# ece411-t14-MetroKnome.net
KiCad netlist of a schematic drawn in EAGLE
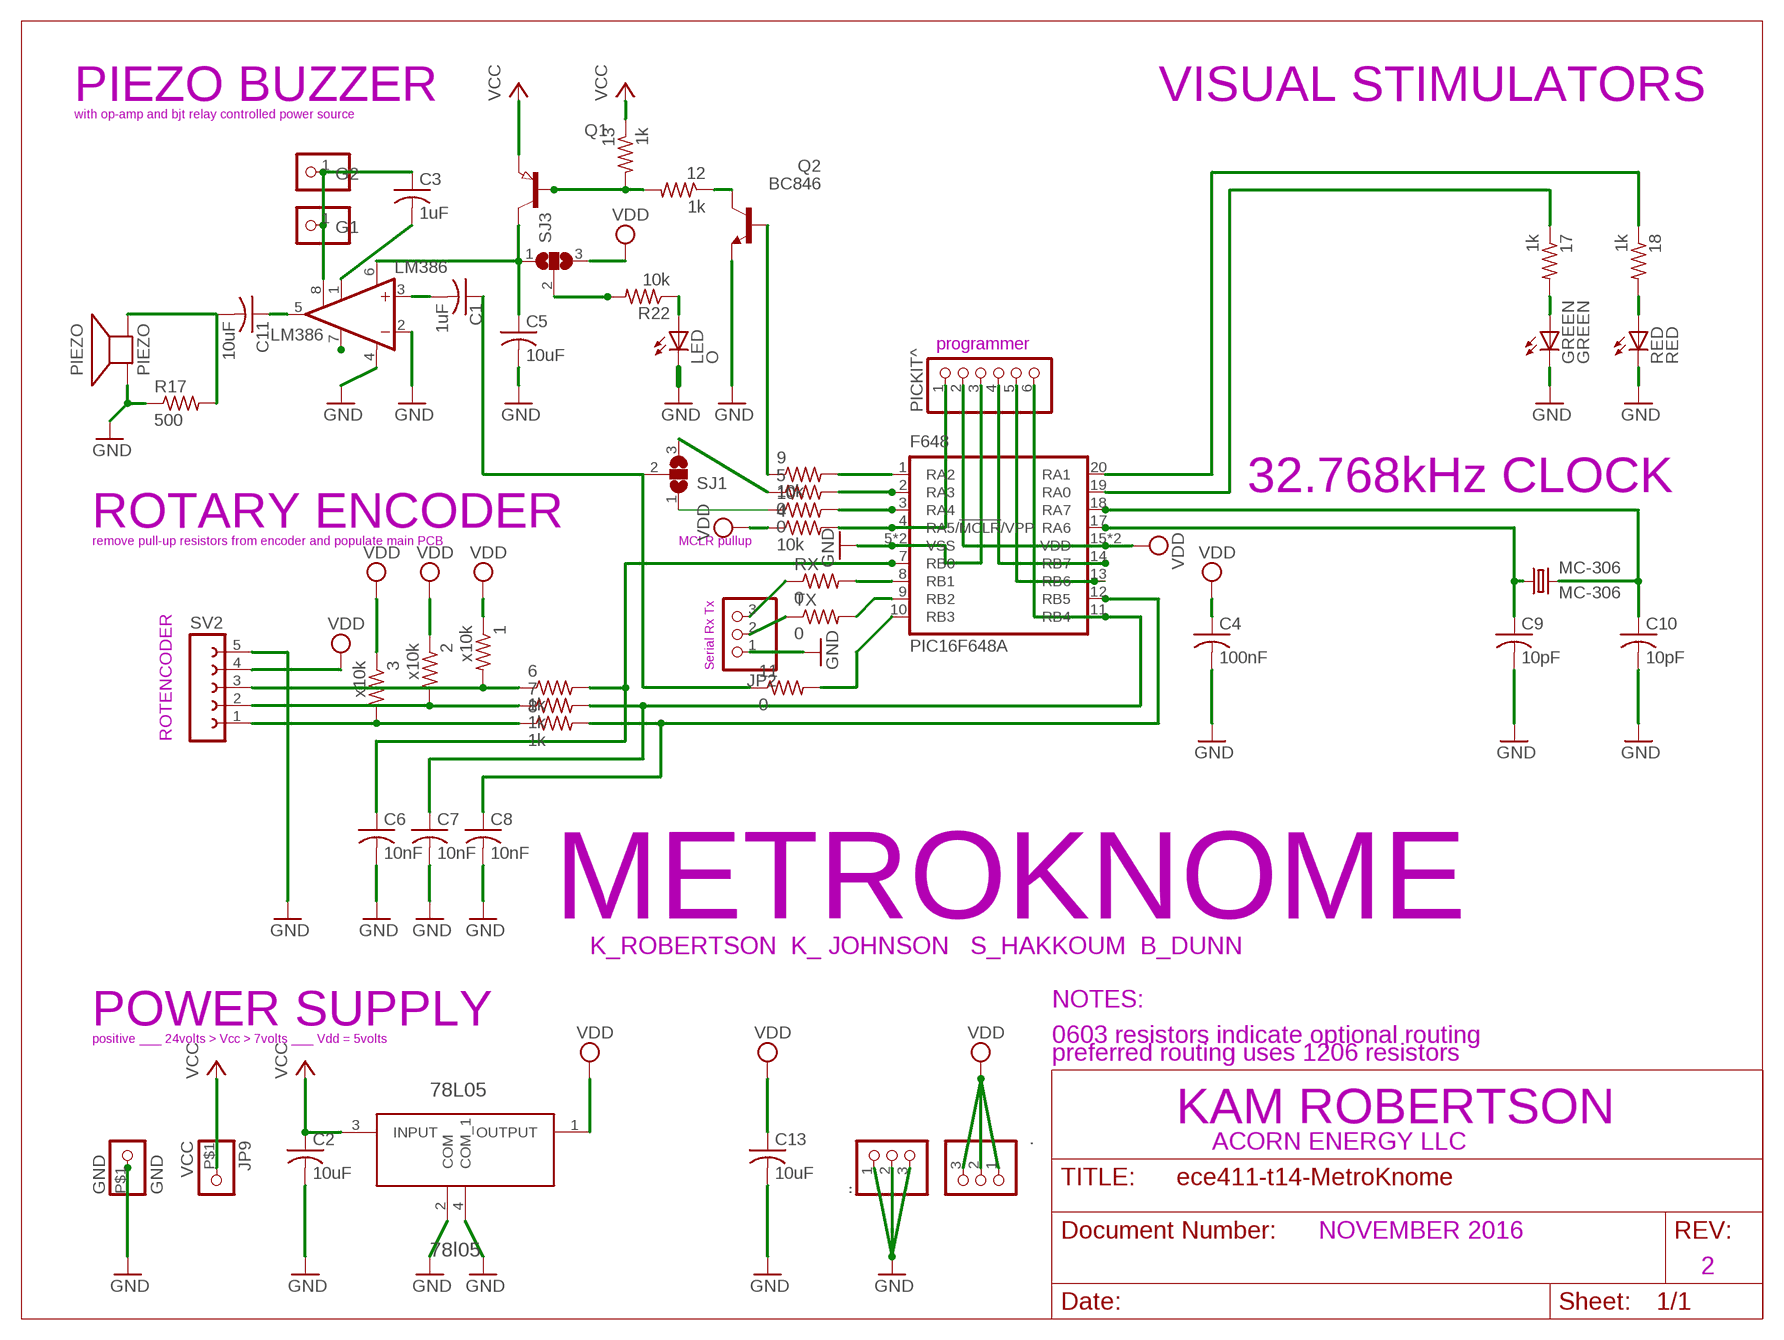
[diagram p0: schematic, sheet 1]

(export (version "E")
  (design (tool "Eeschema 10.0.6"))
  (components
    (comp (ref ".")
      (value "PINHD-1X3CB")
      (footprint "eagle-import:1X03-CLEANBIG")
      (libsource (lib "eagle-import") (part "PINHD-1X3CB"))
    )
    (comp (ref "..")
      (value "PINHD-1X3CB")
      (footprint "eagle-import:1X03-CLEANBIG")
      (libsource (lib "eagle-import") (part "PINHD-1X3CB"))
    )
    (comp (ref "1")
      (value "x10k")
      (footprint "eagle-import:R1206")
      (libsource (lib "eagle-import") (part "R-US_R1206"))
    )
    (comp (ref "2")
      (value "x10k")
      (footprint "eagle-import:R1206")
      (libsource (lib "eagle-import") (part "R-US_R1206"))
    )
    (comp (ref "3")
      (value "x10k")
      (footprint "eagle-import:R1206")
      (libsource (lib "eagle-import") (part "R-US_R1206"))
    )
    (comp (ref "4")
      (value "10k")
      (footprint "eagle-import:R1206")
      (libsource (lib "eagle-import") (part "R-US_R1206"))
    )
    (comp (ref "5")
      (value "0")
      (footprint "eagle-import:R0603")
      (libsource (lib "eagle-import") (part "R-US_R0603"))
    )
    (comp (ref "6")
      (value "1k")
      (footprint "eagle-import:R1206")
      (libsource (lib "eagle-import") (part "R-US_R1206"))
    )
    (comp (ref "7")
      (value "1k")
      (footprint "eagle-import:R1206")
      (libsource (lib "eagle-import") (part "R-US_R1206"))
    )
    (comp (ref "8")
      (value "1k")
      (footprint "eagle-import:R1206")
      (libsource (lib "eagle-import") (part "R-US_R1206"))
    )
    (comp (ref "9")
      (value "10k")
      (footprint "eagle-import:R1206")
      (libsource (lib "eagle-import") (part "R-US_R1206"))
    )
    (comp (ref "10")
      (value "0")
      (footprint "eagle-import:R0603")
      (libsource (lib "eagle-import") (part "R-US_R0603"))
    )
    (comp (ref "11")
      (value "0")
      (footprint "eagle-import:R1206")
      (libsource (lib "eagle-import") (part "R-US_R1206"))
    )
    (comp (ref "12")
      (value "1k")
      (footprint "eagle-import:R1206")
      (libsource (lib "eagle-import") (part "R-US_R1206"))
    )
    (comp (ref "13")
      (value "1k")
      (footprint "eagle-import:R1206")
      (libsource (lib "eagle-import") (part "R-US_R1206"))
    )
    (comp (ref "17")
      (value "1k")
      (footprint "eagle-import:R1206")
      (libsource (lib "eagle-import") (part "R-US_R1206"))
    )
    (comp (ref "18")
      (value "1k")
      (footprint "eagle-import:R1206")
      (libsource (lib "eagle-import") (part "R-US_R1206"))
    )
    (comp (ref "78L05")
      (value "78l05")
      (footprint "eagle-import:SOT150P400X160-4N")
      (fields (field (name "MPN") "UA78L05ACPKG3"))
      (libsource (lib "eagle-import") (part "UA78L05ACPKG3"))
    )
    (comp (ref "C1")
      (value "1uF")
      (footprint "eagle-import:C1210")
      (libsource (lib "eagle-import") (part "C-USC1210"))
    )
    (comp (ref "C2")
      (value "10uF")
      (footprint "eagle-import:C1210")
      (libsource (lib "eagle-import") (part "C-USC1210"))
    )
    (comp (ref "C3")
      (value "1uF")
      (footprint "eagle-import:C1210")
      (libsource (lib "eagle-import") (part "C-USC1210"))
    )
    (comp (ref "C4")
      (value "100nF")
      (footprint "eagle-import:C1210")
      (libsource (lib "eagle-import") (part "C-USC1210"))
    )
    (comp (ref "C5")
      (value "10uF")
      (footprint "eagle-import:C1210")
      (libsource (lib "eagle-import") (part "C-USC1210"))
    )
    (comp (ref "C6")
      (value "10nF")
      (footprint "eagle-import:C1210")
      (libsource (lib "eagle-import") (part "C-USC1210"))
    )
    (comp (ref "C7")
      (value "10nF")
      (footprint "eagle-import:C1210")
      (libsource (lib "eagle-import") (part "C-USC1210"))
    )
    (comp (ref "C8")
      (value "10nF")
      (footprint "eagle-import:C1210")
      (libsource (lib "eagle-import") (part "C-USC1210"))
    )
    (comp (ref "C9")
      (value "10pF")
      (footprint "eagle-import:C1210")
      (libsource (lib "eagle-import") (part "C-USC1210"))
    )
    (comp (ref "C10")
      (value "10pF")
      (footprint "eagle-import:C1210")
      (libsource (lib "eagle-import") (part "C-USC1210"))
    )
    (comp (ref "C11")
      (value "10uF")
      (footprint "eagle-import:C1210")
      (libsource (lib "eagle-import") (part "C-USC1210"))
    )
    (comp (ref "C13")
      (value "10uF")
      (footprint "eagle-import:C1210")
      (libsource (lib "eagle-import") (part "C-USC1210"))
    )
    (comp (ref "F648")
      (value "PIC16F648A")
      (footprint "eagle-import:SSOP20")
      (libsource (lib "eagle-import") (part "PIC16F1826/27SS"))
    )
    (comp (ref "G1")
      (value "PINHD-1X1CB")
      (footprint "eagle-import:1X01-CLEANBIG")
      (libsource (lib "eagle-import") (part "PINHD-1X1CB"))
    )
    (comp (ref "G2")
      (value "PINHD-1X1CB")
      (footprint "eagle-import:1X01-CLEANBIG")
      (libsource (lib "eagle-import") (part "PINHD-1X1CB"))
    )
    (comp (ref "GND")
      (value "GND")
      (footprint "eagle-import:1X1-BIGPOGO")
      (libsource (lib "eagle-import") (part "PINHD-1X1-BIGPOGO"))
    )
    (comp (ref "GREEN")
      (value "GREEN")
      (footprint "eagle-import:LED5MM")
      (libsource (lib "eagle-import") (part "LED5MM"))
    )
    (comp (ref "JP2")
      (value "PINHD-1X3CB")
      (footprint "eagle-import:1X03-CLEANBIG")
      (libsource (lib "eagle-import") (part "PINHD-1X3CB"))
    )
    (comp (ref "JP9")
      (value "VCC")
      (footprint "eagle-import:1X1-BIGPOGO")
      (libsource (lib "eagle-import") (part "PINHD-1X1-BIGPOGO"))
    )
    (comp (ref "LED")
      (value "O")
      (footprint "eagle-import:CHIPLED_1206")
      (libsource (lib "eagle-import") (part "LEDCHIPLED_1206"))
    )
    (comp (ref "LM386")
      (value "LM386")
      (footprint "eagle-import:SO08")
      (libsource (lib "eagle-import") (part "LM386?-M1"))
    )
    (comp (ref "MC-306")
      (value "MC-306")
      (footprint "eagle-import:MC-306")
      (fields
        (field (name "MPN") "MC-306 60.0KHZ  100PPM ,12.5PF")
        (field (name "MPN_1") "MC-306 60.0KHZ  100PPM ,12.5PF")
        (field (name "OC_FARNELL") "1278040")
        (field (name "OC_NEWARK") "31M5576")
      )
      (libsource (lib "eagle-import") (part "MC-306"))
    )
    (comp (ref "PICKIT^")
      (value "PINHD-1X6LOCK")
      (footprint "eagle-import:1X06-BIGLOCK")
      (libsource (lib "eagle-import") (part "PINHD-1X6LOCK"))
    )
    (comp (ref "PIEZO")
      (value "PIEZO")
      (footprint "eagle-import:AL60P")
      (libsource (lib "eagle-import") (part "SPEAKER/AL60P"))
    )
    (comp (ref "Q1")
      (value "PNP-TRANSISTOR_SOT89")
      (footprint "eagle-import:SOT89")
      (libsource (lib "eagle-import") (part "PNP-TRANSISTOR_SOT89"))
    )
    (comp (ref "Q2")
      (value "BC846")
      (footprint "eagle-import:SOT23")
      (libsource (lib "eagle-import") (part "BC846"))
    )
    (comp (ref "R17")
      (value "500")
      (footprint "eagle-import:R1206")
      (libsource (lib "eagle-import") (part "R-US_R1206"))
    )
    (comp (ref "R22")
      (value "10k")
      (footprint "eagle-import:R1206")
      (libsource (lib "eagle-import") (part "R-US_R1206"))
    )
    (comp (ref "RED")
      (value "RED")
      (footprint "eagle-import:LED5MM")
      (libsource (lib "eagle-import") (part "LED5MM"))
    )
    (comp (ref "RX")
      (value "0")
      (footprint "eagle-import:R1206")
      (libsource (lib "eagle-import") (part "R-US_R1206"))
    )
    (comp (ref "SJ1")
      (value "SJ2W")
      (footprint "eagle-import:SJ_2")
      (libsource (lib "eagle-import") (part "SJ2W"))
    )
    (comp (ref "SJ3")
      (value "SJ2W")
      (footprint "eagle-import:SJ_2")
      (libsource (lib "eagle-import") (part "SJ2W"))
    )
    (comp (ref "SV2")
      (value "FE05-1")
      (footprint "eagle-import:FE05-1")
      (libsource (lib "eagle-import") (part "FE05-1"))
    )
    (comp (ref "TX")
      (value "0")
      (footprint "eagle-import:R1206")
      (libsource (lib "eagle-import") (part "R-US_R1206"))
    )
  )
  (nets
    (net (code "1") (name "GND") (class "Default")
      (node (ref "..") (pin "1") (pinfunction "1_1") (pintype "passive"))
      (node (ref "..") (pin "2") (pinfunction "2_2") (pintype "passive"))
      (node (ref "..") (pin "3") (pinfunction "3_3") (pintype "passive"))
      (node (ref "78L05") (pin "2") (pinfunction "COM_2") (pintype "power_in"))
      (node (ref "78L05") (pin "4") (pinfunction "COM_1_4") (pintype "power_in"))
      (node (ref "C10") (pin "2") (pinfunction "2_2") (pintype "passive"))
      (node (ref "C13") (pin "2") (pinfunction "2_2") (pintype "passive"))
      (node (ref "C2") (pin "2") (pinfunction "2_2") (pintype "passive"))
      (node (ref "C4") (pin "2") (pinfunction "2_2") (pintype "passive"))
      (node (ref "C5") (pin "2") (pinfunction "2_2") (pintype "passive"))
      (node (ref "C6") (pin "2") (pinfunction "2_2") (pintype "passive"))
      (node (ref "C7") (pin "2") (pinfunction "2_2") (pintype "passive"))
      (node (ref "C8") (pin "2") (pinfunction "2_2") (pintype "passive"))
      (node (ref "C9") (pin "2") (pinfunction "2_2") (pintype "passive"))
      (node (ref "F648") (pin "5") (pinfunction "VSS_5") (pintype "power_in"))
      (node (ref "F648") (pin "6") (pinfunction "VSS_6") (pintype "power_in"))
      (node (ref "GND") (pin "P$1") (pinfunction "1_P$1") (pintype "passive"))
      (node (ref "GREEN") (pin "K") (pinfunction "C_K") (pintype "passive"))
      (node (ref "JP2") (pin "1") (pinfunction "1_1") (pintype "passive"))
      (node (ref "LED") (pin "C") (pinfunction "C_C") (pintype "passive"))
      (node (ref "LM386") (pin "2") (pinfunction "-IN_2") (pintype "input"))
      (node (ref "LM386") (pin "4") (pinfunction "GND_4") (pintype "power_in"))
      (node (ref "PICKIT^") (pin "3") (pinfunction "3_3") (pintype "passive"))
      (node (ref "PIEZO") (pin "2") (pinfunction "-_2") (pintype "passive"))
      (node (ref "Q2") (pin "2") (pinfunction "E_2") (pintype "passive"))
      (node (ref "R17") (pin "1") (pinfunction "1_1") (pintype "passive"))
      (node (ref "RED") (pin "K") (pinfunction "C_K") (pintype "passive"))
      (node (ref "SV2") (pin "5") (pinfunction "5_5") (pintype "passive"))
    )
    (net (code "2") (name "Net-(1-Pad2)") (class "Default")
      (node (ref "1") (pin "2") (pinfunction "2_2") (pintype "passive"))
      (node (ref "6") (pin "1") (pinfunction "1_1") (pintype "passive"))
      (node (ref "SV2") (pin "3") (pinfunction "3_3") (pintype "passive"))
    )
    (net (code "3") (name "Net-(2-Pad2)") (class "Default")
      (node (ref "2") (pin "2") (pinfunction "2_2") (pintype "passive"))
      (node (ref "7") (pin "1") (pinfunction "1_1") (pintype "passive"))
      (node (ref "SV2") (pin "2") (pinfunction "2_2") (pintype "passive"))
    )
    (net (code "4") (name "Net-(3-Pad2)") (class "Default")
      (node (ref "3") (pin "2") (pinfunction "2_2") (pintype "passive"))
      (node (ref "8") (pin "1") (pinfunction "1_1") (pintype "passive"))
      (node (ref "SV2") (pin "1") (pinfunction "1_1") (pintype "passive"))
    )
    (net (code "5") (name "Net-(5-Pad1)") (class "Default")
      (node (ref "5") (pin "1") (pinfunction "1_1") (pintype "passive"))
      (node (ref "SJ1") (pin "3") (pinfunction "3_3") (pintype "passive"))
    )
    (net (code "6") (name "Net-(10-Pad1)") (class "Default")
      (node (ref "10") (pin "1") (pinfunction "1_1") (pintype "passive"))
      (node (ref "SJ1") (pin "1") (pinfunction "1_1") (pintype "passive"))
    )
    (net (code "7") (name "Net-(11-Pad1)") (class "Default")
      (node (ref "11") (pin "1") (pinfunction "1_1") (pintype "passive"))
      (node (ref "C1") (pin "1") (pinfunction "1_1") (pintype "passive"))
      (node (ref "SJ1") (pin "2") (pinfunction "2_2") (pintype "passive"))
    )
    (net (code "8") (name "Net-(17-Pad2)") (class "Default")
      (node (ref "17") (pin "2") (pinfunction "2_2") (pintype "passive"))
      (node (ref "GREEN") (pin "A") (pinfunction "A_A") (pintype "passive"))
    )
    (net (code "9") (name "Net-(18-Pad2)") (class "Default")
      (node (ref "18") (pin "2") (pinfunction "2_2") (pintype "passive"))
      (node (ref "RED") (pin "A") (pinfunction "A_A") (pintype "passive"))
    )
    (net (code "10") (name "Net-(C3-Pad1)") (class "Default")
      (node (ref "C3") (pin "1") (pinfunction "1_1") (pintype "passive"))
      (node (ref "G1") (pin "1") (pinfunction "1_1") (pintype "passive"))
      (node (ref "G2") (pin "1") (pinfunction "1_1") (pintype "passive"))
      (node (ref "LM386") (pin "8") (pinfunction "GAIN_8") (pintype "passive"))
    )
    (net (code "11") (name "Net-(C3-Pad2)") (class "Default")
      (node (ref "C3") (pin "2") (pinfunction "2_2") (pintype "passive"))
      (node (ref "LM386") (pin "1") (pinfunction "GAIN_1") (pintype "passive"))
    )
    (net (code "12") (name "Net-(F648-RA0)") (class "Default")
      (node (ref "17") (pin "1") (pinfunction "1_1") (pintype "passive"))
      (node (ref "F648") (pin "19") (pinfunction "RA0_19") (pintype "bidirectional"))
    )
    (net (code "13") (name "Net-(F648-RA1)") (class "Default")
      (node (ref "18") (pin "1") (pinfunction "1_1") (pintype "passive"))
      (node (ref "F648") (pin "20") (pinfunction "RA1_20") (pintype "bidirectional"))
    )
    (net (code "14") (name "Net-(F648-RA2)") (class "Default")
      (node (ref "9") (pin "2") (pinfunction "2_2") (pintype "passive"))
      (node (ref "F648") (pin "1") (pinfunction "RA2_1") (pintype "bidirectional"))
    )
    (net (code "15") (name "Net-(F648-RA3)") (class "Default")
      (node (ref "5") (pin "2") (pinfunction "2_2") (pintype "passive"))
      (node (ref "F648") (pin "2") (pinfunction "RA3_2") (pintype "bidirectional"))
    )
    (net (code "16") (name "Net-(F648-RA4)") (class "Default")
      (node (ref "10") (pin "2") (pinfunction "2_2") (pintype "passive"))
      (node (ref "F648") (pin "3") (pinfunction "RA4_3") (pintype "bidirectional"))
    )
    (net (code "17") (name "Net-(F648-RA5{slash}~{MCLR}{slash}VPP)") (class "Default")
      (node (ref "4") (pin "2") (pinfunction "2_2") (pintype "passive"))
      (node (ref "F648") (pin "4") (pinfunction "RA5/~{MCLR}/VPP_4") (pintype "bidirectional"))
      (node (ref "PICKIT^") (pin "1") (pinfunction "1_1") (pintype "passive"))
    )
    (net (code "18") (name "Net-(F648-RA6)") (class "Default")
      (node (ref "C9") (pin "1") (pinfunction "1_1") (pintype "passive"))
      (node (ref "F648") (pin "17") (pinfunction "RA6_17") (pintype "bidirectional"))
      (node (ref "MC-306") (pin "1") (pinfunction "1_1") (pintype "passive"))
    )
    (net (code "19") (name "Net-(F648-RA7)") (class "Default")
      (node (ref "C10") (pin "1") (pinfunction "1_1") (pintype "passive"))
      (node (ref "F648") (pin "18") (pinfunction "RA7_18") (pintype "bidirectional"))
      (node (ref "MC-306") (pin "4") (pinfunction "2_4") (pintype "passive"))
    )
    (net (code "20") (name "Net-(F648-RB0)") (class "Default")
      (node (ref "6") (pin "2") (pinfunction "2_2") (pintype "passive"))
      (node (ref "C6") (pin "1") (pinfunction "1_1") (pintype "passive"))
      (node (ref "F648") (pin "7") (pinfunction "RB0_7") (pintype "bidirectional"))
    )
    (net (code "21") (name "Net-(F648-RB1)") (class "Default")
      (node (ref "F648") (pin "8") (pinfunction "RB1_8") (pintype "bidirectional"))
      (node (ref "RX") (pin "2") (pinfunction "2_2") (pintype "passive"))
    )
    (net (code "22") (name "Net-(F648-RB2)") (class "Default")
      (node (ref "F648") (pin "9") (pinfunction "RB2_9") (pintype "bidirectional"))
      (node (ref "TX") (pin "2") (pinfunction "2_2") (pintype "passive"))
    )
    (net (code "23") (name "Net-(F648-RB3)") (class "Default")
      (node (ref "11") (pin "2") (pinfunction "2_2") (pintype "passive"))
      (node (ref "F648") (pin "10") (pinfunction "RB3_10") (pintype "bidirectional"))
    )
    (net (code "24") (name "Net-(F648-RB4)") (class "Default")
      (node (ref "7") (pin "2") (pinfunction "2_2") (pintype "passive"))
      (node (ref "C7") (pin "1") (pinfunction "1_1") (pintype "passive"))
      (node (ref "F648") (pin "11") (pinfunction "RB4_11") (pintype "bidirectional"))
      (node (ref "PICKIT^") (pin "6") (pinfunction "6_6") (pintype "passive"))
    )
    (net (code "25") (name "Net-(F648-RB5)") (class "Default")
      (node (ref "8") (pin "2") (pinfunction "2_2") (pintype "passive"))
      (node (ref "C8") (pin "1") (pinfunction "1_1") (pintype "passive"))
      (node (ref "F648") (pin "12") (pinfunction "RB5_12") (pintype "bidirectional"))
    )
    (net (code "26") (name "Net-(F648-RB6)") (class "Default")
      (node (ref "F648") (pin "13") (pinfunction "RB6_13") (pintype "bidirectional"))
      (node (ref "PICKIT^") (pin "5") (pinfunction "5_5") (pintype "passive"))
    )
    (net (code "27") (name "Net-(F648-RB7)") (class "Default")
      (node (ref "F648") (pin "14") (pinfunction "RB7_14") (pintype "bidirectional"))
      (node (ref "PICKIT^") (pin "4") (pinfunction "4_4") (pintype "passive"))
    )
    (net (code "28") (name "Net-(JP2-Pad2)") (class "Default")
      (node (ref "JP2") (pin "2") (pinfunction "2_2") (pintype "passive"))
      (node (ref "TX") (pin "1") (pinfunction "1_1") (pintype "passive"))
    )
    (net (code "29") (name "Net-(JP2-Pad3)") (class "Default")
      (node (ref "JP2") (pin "3") (pinfunction "3_3") (pintype "passive"))
      (node (ref "RX") (pin "1") (pinfunction "1_1") (pintype "passive"))
    )
    (net (code "30") (name "Net-(LED-PadA)") (class "Default")
      (node (ref "LED") (pin "A") (pinfunction "A_A") (pintype "passive"))
      (node (ref "R22") (pin "1") (pinfunction "1_1") (pintype "passive"))
    )
    (net (code "31") (name "Net-(LM386-+IN)") (class "Default")
      (node (ref "C1") (pin "2") (pinfunction "2_2") (pintype "passive"))
      (node (ref "LM386") (pin "3") (pinfunction "+IN_3") (pintype "input"))
    )
    (net (code "32") (name "Net-(LM386-OUT)") (class "Default")
      (node (ref "C11") (pin "1") (pinfunction "1_1") (pintype "passive"))
      (node (ref "LM386") (pin "5") (pinfunction "OUT_5") (pintype "output"))
    )
    (net (code "33") (name "Net-(LM386-VS)") (class "Default")
      (node (ref "C5") (pin "1") (pinfunction "1_1") (pintype "passive"))
      (node (ref "LM386") (pin "6") (pinfunction "VS_6") (pintype "power_in"))
      (node (ref "Q1") (pin "2") (pinfunction "C_2") (pintype "passive"))
      (node (ref "SJ3") (pin "1") (pinfunction "1_1") (pintype "passive"))
    )
    (net (code "34") (name "Net-(PIEZO-+)") (class "Default")
      (node (ref "C11") (pin "2") (pinfunction "2_2") (pintype "passive"))
      (node (ref "PIEZO") (pin "1") (pinfunction "+_1") (pintype "passive"))
      (node (ref "R17") (pin "2") (pinfunction "2_2") (pintype "passive"))
    )
    (net (code "35") (name "Net-(Q1-B)") (class "Default")
      (node (ref "12") (pin "2") (pinfunction "2_2") (pintype "passive"))
      (node (ref "13") (pin "2") (pinfunction "2_2") (pintype "passive"))
      (node (ref "Q1") (pin "1") (pinfunction "B_1") (pintype "passive"))
    )
    (net (code "36") (name "Net-(Q2-B)") (class "Default")
      (node (ref "9") (pin "1") (pinfunction "1_1") (pintype "passive"))
      (node (ref "Q2") (pin "1") (pinfunction "B_1") (pintype "passive"))
    )
    (net (code "37") (name "Net-(Q2-C)") (class "Default")
      (node (ref "12") (pin "1") (pinfunction "1_1") (pintype "passive"))
      (node (ref "Q2") (pin "3") (pinfunction "C_3") (pintype "passive"))
    )
    (net (code "38") (name "Net-(R22-Pad2)") (class "Default")
      (node (ref "R22") (pin "2") (pinfunction "2_2") (pintype "passive"))
      (node (ref "SJ3") (pin "2") (pinfunction "2_2") (pintype "passive"))
    )
    (net (code "39") (name "VCC") (class "Default")
      (node (ref "13") (pin "1") (pinfunction "1_1") (pintype "passive"))
      (node (ref "78L05") (pin "3") (pinfunction "INPUT_3") (pintype "input"))
      (node (ref "C2") (pin "1") (pinfunction "1_1") (pintype "passive"))
      (node (ref "JP9") (pin "P$1") (pinfunction "1_P$1") (pintype "passive"))
      (node (ref "Q1") (pin "3") (pinfunction "E_3") (pintype "passive"))
    )
    (net (code "40") (name "VDD") (class "Default")
      (node (ref ".") (pin "1") (pinfunction "1_1") (pintype "passive"))
      (node (ref ".") (pin "2") (pinfunction "2_2") (pintype "passive"))
      (node (ref ".") (pin "3") (pinfunction "3_3") (pintype "passive"))
      (node (ref "1") (pin "1") (pinfunction "1_1") (pintype "passive"))
      (node (ref "2") (pin "1") (pinfunction "1_1") (pintype "passive"))
      (node (ref "3") (pin "1") (pinfunction "1_1") (pintype "passive"))
      (node (ref "4") (pin "1") (pinfunction "1_1") (pintype "passive"))
      (node (ref "78L05") (pin "1") (pinfunction "OUTPUT_1") (pintype "output"))
      (node (ref "C13") (pin "1") (pinfunction "1_1") (pintype "passive"))
      (node (ref "C4") (pin "1") (pinfunction "1_1") (pintype "passive"))
      (node (ref "F648") (pin "15") (pinfunction "VDD_15") (pintype "power_in"))
      (node (ref "F648") (pin "16") (pinfunction "VDD_16") (pintype "power_in"))
      (node (ref "PICKIT^") (pin "2") (pinfunction "2_2") (pintype "passive"))
      (node (ref "SJ3") (pin "3") (pinfunction "3_3") (pintype "passive"))
      (node (ref "SV2") (pin "4") (pinfunction "4_4") (pintype "passive"))
    )
    (net (code "41") (name "unconnected-(LM386-BYPASS-Pad7)") (class "Default")
      (node (ref "LM386") (pin "7") (pinfunction "BYPASS_7") (pintype "passive"))
    )
  )
)
